# Nucleo.net
KiCad netlist of a schematic drawn in Altium Designer
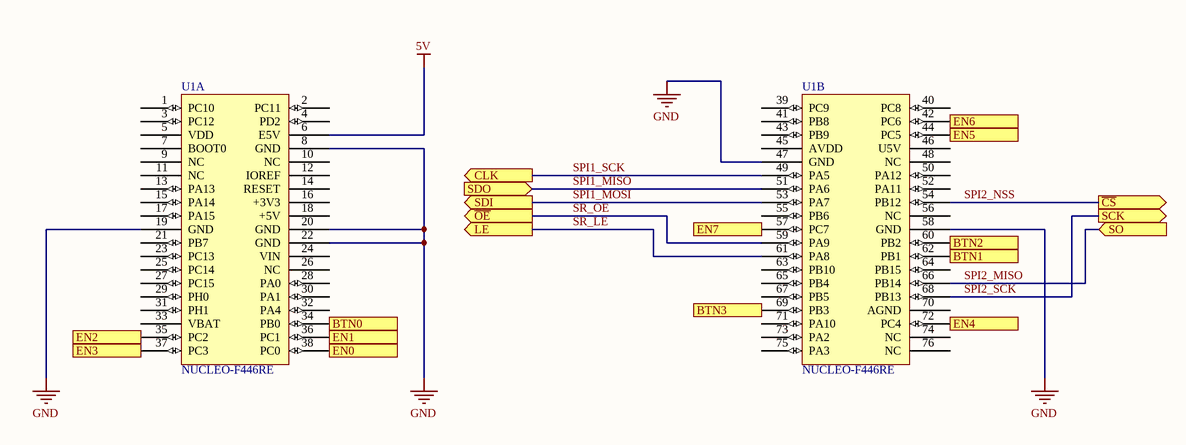
[diagram p0: Nucleo.SchDoc]

(export (version "E")
  (design (tool "Eeschema 10.0.6"))
  (components
    (comp (ref "U1")
      (value "NUCLEO-F446RE")
      (footprint "FP_NUCLEO-64")
      (libsource (lib "hallglib") (part "NUCLEO-F446RE"))
    )
  )
  (nets
    (net (code "1") (name "/BTN0") (class "Default")
      (node (ref "U1") (pin "34") (pinfunction "PB0_34") (pintype "bidirectional"))
    )
    (net (code "2") (name "/BTN1") (class "Default")
      (node (ref "U1") (pin "62") (pinfunction "PB1_62") (pintype "bidirectional"))
    )
    (net (code "3") (name "/BTN2") (class "Default")
      (node (ref "U1") (pin "60") (pinfunction "PB2_60") (pintype "bidirectional"))
    )
    (net (code "4") (name "/BTN3") (class "Default")
      (node (ref "U1") (pin "69") (pinfunction "PB3_69") (pintype "bidirectional"))
    )
    (net (code "5") (name "/EN0") (class "Default")
      (node (ref "U1") (pin "38") (pinfunction "PC0_38") (pintype "bidirectional"))
    )
    (net (code "6") (name "/EN1") (class "Default")
      (node (ref "U1") (pin "36") (pinfunction "PC1_36") (pintype "bidirectional"))
    )
    (net (code "7") (name "/EN2") (class "Default")
      (node (ref "U1") (pin "35") (pinfunction "PC2_35") (pintype "bidirectional"))
    )
    (net (code "8") (name "/EN3") (class "Default")
      (node (ref "U1") (pin "37") (pinfunction "PC3_37") (pintype "bidirectional"))
    )
    (net (code "9") (name "/EN4") (class "Default")
      (node (ref "U1") (pin "72") (pinfunction "PC4_72") (pintype "bidirectional"))
    )
    (net (code "10") (name "/EN5") (class "Default")
      (node (ref "U1") (pin "44") (pinfunction "PC5_44") (pintype "bidirectional"))
    )
    (net (code "11") (name "/EN6") (class "Default")
      (node (ref "U1") (pin "42") (pinfunction "PC6_42") (pintype "bidirectional"))
    )
    (net (code "12") (name "/EN7") (class "Default")
      (node (ref "U1") (pin "57") (pinfunction "PC7_57") (pintype "bidirectional"))
    )
    (net (code "13") (name "/SPI1_MISO") (class "Default")
      (node (ref "U1") (pin "51") (pinfunction "PA6_51") (pintype "bidirectional"))
    )
    (net (code "14") (name "/SPI1_MOSI") (class "Default")
      (node (ref "U1") (pin "53") (pinfunction "PA7_53") (pintype "bidirectional"))
    )
    (net (code "15") (name "/SPI1_SCK") (class "Default")
      (node (ref "U1") (pin "49") (pinfunction "PA5_49") (pintype "bidirectional"))
    )
    (net (code "16") (name "/SPI2_MISO") (class "Default")
      (node (ref "U1") (pin "66") (pinfunction "PB14_66") (pintype "bidirectional"))
    )
    (net (code "17") (name "/SPI2_NSS") (class "Default")
      (node (ref "U1") (pin "54") (pinfunction "PB12_54") (pintype "bidirectional"))
    )
    (net (code "18") (name "/SPI2_SCK") (class "Default")
      (node (ref "U1") (pin "68") (pinfunction "PB13_68") (pintype "bidirectional"))
    )
    (net (code "19") (name "/SR_LE") (class "Default")
      (node (ref "U1") (pin "61") (pinfunction "PA8_61") (pintype "bidirectional"))
    )
    (net (code "20") (name "/SR_~{OE}") (class "Default")
      (node (ref "U1") (pin "59") (pinfunction "PA9_59") (pintype "bidirectional"))
    )
    (net (code "21") (name "5V") (class "Default")
      (node (ref "U1") (pin "6") (pinfunction "E5V_6") (pintype "power_in"))
    )
    (net (code "22") (name "GND") (class "Default")
      (node (ref "U1") (pin "19") (pinfunction "GND_19") (pintype "passive"))
      (node (ref "U1") (pin "20") (pinfunction "GND_20") (pintype "passive"))
      (node (ref "U1") (pin "22") (pinfunction "GND_22") (pintype "passive"))
      (node (ref "U1") (pin "47") (pinfunction "GND_47") (pintype "passive"))
      (node (ref "U1") (pin "58") (pinfunction "GND_58") (pintype "passive"))
      (node (ref "U1") (pin "8") (pinfunction "GND_8") (pintype "passive"))
    )
    (net (code "23") (name "unconnected-(U1A-+3V3-Pad16)") (class "Default")
      (node (ref "U1") (pin "16") (pinfunction "+3V3_16") (pintype "power_in"))
    )
    (net (code "24") (name "unconnected-(U1A-+5V-Pad18)") (class "Default")
      (node (ref "U1") (pin "18") (pinfunction "+5V_18") (pintype "power_in"))
    )
    (net (code "25") (name "unconnected-(U1A-BOOT0-Pad7)") (class "Default")
      (node (ref "U1") (pin "7") (pinfunction "BOOT0_7") (pintype "passive"))
    )
    (net (code "26") (name "unconnected-(U1A-IOREF-Pad12)") (class "Default")
      (node (ref "U1") (pin "12") (pinfunction "IOREF_12") (pintype "passive"))
    )
    (net (code "27") (name "unconnected-(U1A-NC-Pad9)") (class "Default")
      (node (ref "U1") (pin "9") (pinfunction "NC_9") (pintype "passive"))
    )
    (net (code "28") (name "unconnected-(U1A-NC-Pad10)") (class "Default")
      (node (ref "U1") (pin "10") (pinfunction "NC_10") (pintype "passive"))
    )
    (net (code "29") (name "unconnected-(U1A-NC-Pad11)") (class "Default")
      (node (ref "U1") (pin "11") (pinfunction "NC_11") (pintype "passive"))
    )
    (net (code "30") (name "unconnected-(U1A-NC-Pad26)") (class "Default")
      (node (ref "U1") (pin "26") (pinfunction "NC_26") (pintype "passive"))
    )
    (net (code "31") (name "unconnected-(U1A-PA0-Pad28)") (class "Default")
      (node (ref "U1") (pin "28") (pinfunction "PA0_28") (pintype "bidirectional"))
    )
    (net (code "32") (name "unconnected-(U1A-PA1-Pad30)") (class "Default")
      (node (ref "U1") (pin "30") (pinfunction "PA1_30") (pintype "bidirectional"))
    )
    (net (code "33") (name "unconnected-(U1A-PA4-Pad32)") (class "Default")
      (node (ref "U1") (pin "32") (pinfunction "PA4_32") (pintype "bidirectional"))
    )
    (net (code "34") (name "unconnected-(U1A-PA13-Pad13)") (class "Default")
      (node (ref "U1") (pin "13") (pinfunction "PA13_13") (pintype "bidirectional"))
    )
    (net (code "35") (name "unconnected-(U1A-PA14-Pad15)") (class "Default")
      (node (ref "U1") (pin "15") (pinfunction "PA14_15") (pintype "bidirectional"))
    )
    (net (code "36") (name "unconnected-(U1A-PA15-Pad17)") (class "Default")
      (node (ref "U1") (pin "17") (pinfunction "PA15_17") (pintype "bidirectional"))
    )
    (net (code "37") (name "unconnected-(U1A-PB7-Pad21)") (class "Default")
      (node (ref "U1") (pin "21") (pinfunction "PB7_21") (pintype "bidirectional"))
    )
    (net (code "38") (name "unconnected-(U1A-PC10-Pad1)") (class "Default")
      (node (ref "U1") (pin "1") (pinfunction "PC10_1") (pintype "bidirectional"))
    )
    (net (code "39") (name "unconnected-(U1A-PC11-Pad2)") (class "Default")
      (node (ref "U1") (pin "2") (pinfunction "PC11_2") (pintype "bidirectional"))
    )
    (net (code "40") (name "unconnected-(U1A-PC12-Pad3)") (class "Default")
      (node (ref "U1") (pin "3") (pinfunction "PC12_3") (pintype "bidirectional"))
    )
    (net (code "41") (name "unconnected-(U1A-PC13-Pad23)") (class "Default")
      (node (ref "U1") (pin "23") (pinfunction "PC13_23") (pintype "bidirectional"))
    )
    (net (code "42") (name "unconnected-(U1A-PC14-Pad25)") (class "Default")
      (node (ref "U1") (pin "25") (pinfunction "PC14_25") (pintype "bidirectional"))
    )
    (net (code "43") (name "unconnected-(U1A-PC15-Pad27)") (class "Default")
      (node (ref "U1") (pin "27") (pinfunction "PC15_27") (pintype "bidirectional"))
    )
    (net (code "44") (name "unconnected-(U1A-PD2-Pad4)") (class "Default")
      (node (ref "U1") (pin "4") (pinfunction "PD2_4") (pintype "bidirectional"))
    )
    (net (code "45") (name "unconnected-(U1A-PH0-Pad29)") (class "Default")
      (node (ref "U1") (pin "29") (pinfunction "PH0_29") (pintype "bidirectional"))
    )
    (net (code "46") (name "unconnected-(U1A-PH1-Pad31)") (class "Default")
      (node (ref "U1") (pin "31") (pinfunction "PH1_31") (pintype "bidirectional"))
    )
    (net (code "47") (name "unconnected-(U1A-RESET-Pad14)") (class "Default")
      (node (ref "U1") (pin "14") (pinfunction "RESET_14") (pintype "passive"))
    )
    (net (code "48") (name "unconnected-(U1A-VBAT-Pad33)") (class "Default")
      (node (ref "U1") (pin "33") (pinfunction "VBAT_33") (pintype "power_in"))
    )
    (net (code "49") (name "unconnected-(U1A-VDD-Pad5)") (class "Default")
      (node (ref "U1") (pin "5") (pinfunction "VDD_5") (pintype "power_in"))
    )
    (net (code "50") (name "unconnected-(U1A-VIN-Pad24)") (class "Default")
      (node (ref "U1") (pin "24") (pinfunction "VIN_24") (pintype "power_in"))
    )
    (net (code "51") (name "unconnected-(U1B-AGND-Pad70)") (class "Default")
      (node (ref "U1") (pin "70") (pinfunction "AGND_70") (pintype "passive"))
    )
    (net (code "52") (name "unconnected-(U1B-AVDD-Pad45)") (class "Default")
      (node (ref "U1") (pin "45") (pinfunction "AVDD_45") (pintype "power_in"))
    )
    (net (code "53") (name "unconnected-(U1B-NC-Pad48)") (class "Default")
      (node (ref "U1") (pin "48") (pinfunction "NC_48") (pintype "passive"))
    )
    (net (code "54") (name "unconnected-(U1B-NC-Pad56)") (class "Default")
      (node (ref "U1") (pin "56") (pinfunction "NC_56") (pintype "passive"))
    )
    (net (code "55") (name "unconnected-(U1B-NC-Pad74)") (class "Default")
      (node (ref "U1") (pin "74") (pinfunction "NC_74") (pintype "passive"))
    )
    (net (code "56") (name "unconnected-(U1B-NC-Pad76)") (class "Default")
      (node (ref "U1") (pin "76") (pinfunction "NC_76") (pintype "passive"))
    )
    (net (code "57") (name "unconnected-(U1B-PA2-Pad73)") (class "Default")
      (node (ref "U1") (pin "73") (pinfunction "PA2_73") (pintype "bidirectional"))
    )
    (net (code "58") (name "unconnected-(U1B-PA3-Pad75)") (class "Default")
      (node (ref "U1") (pin "75") (pinfunction "PA3_75") (pintype "bidirectional"))
    )
    (net (code "59") (name "unconnected-(U1B-PA10-Pad71)") (class "Default")
      (node (ref "U1") (pin "71") (pinfunction "PA10_71") (pintype "bidirectional"))
    )
    (net (code "60") (name "unconnected-(U1B-PA11-Pad52)") (class "Default")
      (node (ref "U1") (pin "52") (pinfunction "PA11_52") (pintype "bidirectional"))
    )
    (net (code "61") (name "unconnected-(U1B-PA12-Pad50)") (class "Default")
      (node (ref "U1") (pin "50") (pinfunction "PA12_50") (pintype "bidirectional"))
    )
    (net (code "62") (name "unconnected-(U1B-PB4-Pad65)") (class "Default")
      (node (ref "U1") (pin "65") (pinfunction "PB4_65") (pintype "bidirectional"))
    )
    (net (code "63") (name "unconnected-(U1B-PB5-Pad67)") (class "Default")
      (node (ref "U1") (pin "67") (pinfunction "PB5_67") (pintype "bidirectional"))
    )
    (net (code "64") (name "unconnected-(U1B-PB6-Pad55)") (class "Default")
      (node (ref "U1") (pin "55") (pinfunction "PB6_55") (pintype "bidirectional"))
    )
    (net (code "65") (name "unconnected-(U1B-PB8-Pad41)") (class "Default")
      (node (ref "U1") (pin "41") (pinfunction "PB8_41") (pintype "bidirectional"))
    )
    (net (code "66") (name "unconnected-(U1B-PB9-Pad43)") (class "Default")
      (node (ref "U1") (pin "43") (pinfunction "PB9_43") (pintype "bidirectional"))
    )
    (net (code "67") (name "unconnected-(U1B-PB10-Pad63)") (class "Default")
      (node (ref "U1") (pin "63") (pinfunction "PB10_63") (pintype "bidirectional"))
    )
    (net (code "68") (name "unconnected-(U1B-PB15-Pad64)") (class "Default")
      (node (ref "U1") (pin "64") (pinfunction "PB15_64") (pintype "bidirectional"))
    )
    (net (code "69") (name "unconnected-(U1B-PC8-Pad40)") (class "Default")
      (node (ref "U1") (pin "40") (pinfunction "PC8_40") (pintype "bidirectional"))
    )
    (net (code "70") (name "unconnected-(U1B-PC9-Pad39)") (class "Default")
      (node (ref "U1") (pin "39") (pinfunction "PC9_39") (pintype "bidirectional"))
    )
    (net (code "71") (name "unconnected-(U1B-U5V-Pad46)") (class "Default")
      (node (ref "U1") (pin "46") (pinfunction "U5V_46") (pintype "power_in"))
    )
  )
)
